# 04-MCU.net
KiCad netlist of a schematic drawn in Altium Designer
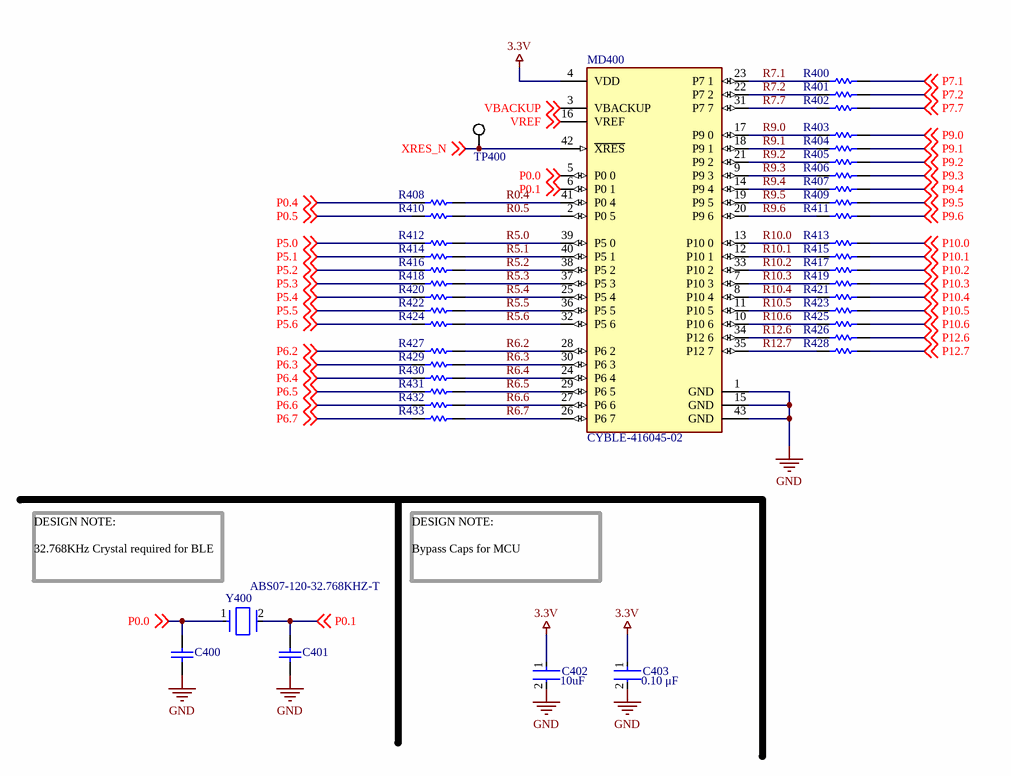
[diagram p0: 04-MCU.SchDoc]

(export (version "E")
  (design (tool "Eeschema 10.0.6"))
  (components
    (comp (ref "C400")
      (value "08055A6R0CAT2A")
      (footprint "CAPC2013X94X50LL20T25")
      (fields (field (name "MANUFACTURER") "AVX Interconnect / Elco"))
      (libsource (lib "Altium Content Vault") (part "CAP"))
    )
    (comp (ref "C401")
      (value "08055A6R0CAT2A")
      (footprint "CAPC2013X94X50LL20T25")
      (fields (field (name "MANUFACTURER") "AVX Interconnect / Elco"))
      (libsource (lib "Altium Content Vault") (part "CAP"))
    )
    (comp (ref "C402")
      (value "10uF")
      (footprint "FP-C0805C-DG-MFG")
      (description "CAP CER 10UF 10V X5R 0805")
      (fields
        (field (name "MANUFACTURER") "Kemet")
        (field (name "MANUFACTURER PART NUMBER") "C0805C106K8PACTU")
      )
      (libsource (lib "Altium Content Vault") (part "11868f565c42a9108669ba33697ecf6"))
    )
    (comp (ref "C403")
      (value "0.10 μF")
      (footprint "FP-C0805C-DN-MFG")
      (description "CAP CER 0.1UF 50V X7R 0805")
      (fields
        (field (name "MANUFACTURER") "KEMET")
        (field (name "MANUFACTURER PART NUMBER") "C0805C104K5RACTU")
      )
      (libsource (lib "Altium Content Vault") (part "b4654b650e69147ec39a6b967a45e02"))
    )
    (comp (ref "MD400")
      (value "CYBLE-416045-02")
      (footprint "FP-CYBLE-416045-02-MFG")
      (description "RF TXRX MOD BLUETOOTH TRACE ANT")
      (fields
        (field (name "OCTOPART") "https://octopart.com/cyble-416045-02-cypress+semiconductor-96386825")
        (field (name "MANUFACTURER") "Cypress Semiconductor")
      )
      (libsource (lib "Altium Content Vault") (part "10a29a4e77099fbb6f911efb04878b1"))
    )
    (comp (ref "R400")
      (value "ERA6AEB101V")
      (footprint "RESC2013X60X40ML20T25")
      (fields (field (name "MANUFACTURER") "Panasonic"))
      (libsource (lib "Altium Content Vault") (part "RES"))
    )
    (comp (ref "R401")
      (value "ERA6AEB101V")
      (footprint "RESC2013X60X40ML20T25")
      (fields (field (name "MANUFACTURER") "Panasonic"))
      (libsource (lib "Altium Content Vault") (part "RES"))
    )
    (comp (ref "R402")
      (value "ERA6AEB101V")
      (footprint "RESC2013X60X40ML20T25")
      (fields (field (name "MANUFACTURER") "Panasonic"))
      (libsource (lib "Altium Content Vault") (part "RES"))
    )
    (comp (ref "R403")
      (value "ERA6AEB101V")
      (footprint "RESC2013X60X40ML20T25")
      (fields (field (name "MANUFACTURER") "Panasonic"))
      (libsource (lib "Altium Content Vault") (part "RES"))
    )
    (comp (ref "R404")
      (value "ERA6AEB101V")
      (footprint "RESC2013X60X40ML20T25")
      (fields (field (name "MANUFACTURER") "Panasonic"))
      (libsource (lib "Altium Content Vault") (part "RES"))
    )
    (comp (ref "R405")
      (value "ERA6AEB101V")
      (footprint "RESC2013X60X40ML20T25")
      (fields (field (name "MANUFACTURER") "Panasonic"))
      (libsource (lib "Altium Content Vault") (part "RES"))
    )
    (comp (ref "R406")
      (value "ERA6AEB101V")
      (footprint "RESC2013X60X40ML20T25")
      (fields (field (name "MANUFACTURER") "Panasonic"))
      (libsource (lib "Altium Content Vault") (part "RES"))
    )
    (comp (ref "R407")
      (value "ERA6AEB101V")
      (footprint "RESC2013X60X40ML20T25")
      (fields (field (name "MANUFACTURER") "Panasonic"))
      (libsource (lib "Altium Content Vault") (part "RES"))
    )
    (comp (ref "R408")
      (value "ERA6AEB101V")
      (footprint "RESC2013X60X40ML20T25")
      (fields (field (name "MANUFACTURER") "Panasonic"))
      (libsource (lib "Altium Content Vault") (part "RES"))
    )
    (comp (ref "R409")
      (value "ERA6AEB101V")
      (footprint "RESC2013X60X40ML20T25")
      (fields (field (name "MANUFACTURER") "Panasonic"))
      (libsource (lib "Altium Content Vault") (part "RES"))
    )
    (comp (ref "R410")
      (value "ERA6AEB101V")
      (footprint "RESC2013X60X40ML20T25")
      (fields (field (name "MANUFACTURER") "Panasonic"))
      (libsource (lib "Altium Content Vault") (part "RES"))
    )
    (comp (ref "R411")
      (value "ERA6AEB101V")
      (footprint "RESC2013X60X40ML20T25")
      (fields (field (name "MANUFACTURER") "Panasonic"))
      (libsource (lib "Altium Content Vault") (part "RES"))
    )
    (comp (ref "R412")
      (value "ERA6AEB101V")
      (footprint "RESC2013X60X40ML20T25")
      (fields (field (name "MANUFACTURER") "Panasonic"))
      (libsource (lib "Altium Content Vault") (part "RES"))
    )
    (comp (ref "R413")
      (value "ERA6AEB101V")
      (footprint "RESC2013X60X40ML20T25")
      (fields (field (name "MANUFACTURER") "Panasonic"))
      (libsource (lib "Altium Content Vault") (part "RES"))
    )
    (comp (ref "R414")
      (value "ERA6AEB101V")
      (footprint "RESC2013X60X40ML20T25")
      (fields (field (name "MANUFACTURER") "Panasonic"))
      (libsource (lib "Altium Content Vault") (part "RES"))
    )
    (comp (ref "R415")
      (value "ERA6AEB101V")
      (footprint "RESC2013X60X40ML20T25")
      (fields (field (name "MANUFACTURER") "Panasonic"))
      (libsource (lib "Altium Content Vault") (part "RES"))
    )
    (comp (ref "R416")
      (value "ERA6AEB101V")
      (footprint "RESC2013X60X40ML20T25")
      (fields (field (name "MANUFACTURER") "Panasonic"))
      (libsource (lib "Altium Content Vault") (part "RES"))
    )
    (comp (ref "R417")
      (value "ERA6AEB101V")
      (footprint "RESC2013X60X40ML20T25")
      (fields (field (name "MANUFACTURER") "Panasonic"))
      (libsource (lib "Altium Content Vault") (part "RES"))
    )
    (comp (ref "R418")
      (value "ERA6AEB101V")
      (footprint "RESC2013X60X40ML20T25")
      (fields (field (name "MANUFACTURER") "Panasonic"))
      (libsource (lib "Altium Content Vault") (part "RES"))
    )
    (comp (ref "R419")
      (value "ERA6AEB101V")
      (footprint "RESC2013X60X40ML20T25")
      (fields (field (name "MANUFACTURER") "Panasonic"))
      (libsource (lib "Altium Content Vault") (part "RES"))
    )
    (comp (ref "R420")
      (value "ERA6AEB101V")
      (footprint "RESC2013X60X40ML20T25")
      (fields (field (name "MANUFACTURER") "Panasonic"))
      (libsource (lib "Altium Content Vault") (part "RES"))
    )
    (comp (ref "R421")
      (value "ERA6AEB101V")
      (footprint "RESC2013X60X40ML20T25")
      (fields (field (name "MANUFACTURER") "Panasonic"))
      (libsource (lib "Altium Content Vault") (part "RES"))
    )
    (comp (ref "R422")
      (value "ERA6AEB101V")
      (footprint "RESC2013X60X40ML20T25")
      (fields (field (name "MANUFACTURER") "Panasonic"))
      (libsource (lib "Altium Content Vault") (part "RES"))
    )
    (comp (ref "R423")
      (value "ERA6AEB101V")
      (footprint "RESC2013X60X40ML20T25")
      (fields (field (name "MANUFACTURER") "Panasonic"))
      (libsource (lib "Altium Content Vault") (part "RES"))
    )
    (comp (ref "R424")
      (value "ERA6AEB101V")
      (footprint "RESC2013X60X40ML20T25")
      (fields (field (name "MANUFACTURER") "Panasonic"))
      (libsource (lib "Altium Content Vault") (part "RES"))
    )
    (comp (ref "R425")
      (value "ERA6AEB101V")
      (footprint "RESC2013X60X40ML20T25")
      (fields (field (name "MANUFACTURER") "Panasonic"))
      (libsource (lib "Altium Content Vault") (part "RES"))
    )
    (comp (ref "R426")
      (value "ERA6AEB101V")
      (footprint "RESC2013X60X40ML20T25")
      (fields (field (name "MANUFACTURER") "Panasonic"))
      (libsource (lib "Altium Content Vault") (part "RES"))
    )
    (comp (ref "R427")
      (value "ERA6AEB101V")
      (footprint "RESC2013X60X40ML20T25")
      (fields (field (name "MANUFACTURER") "Panasonic"))
      (libsource (lib "Altium Content Vault") (part "RES"))
    )
    (comp (ref "R428")
      (value "ERA6AEB101V")
      (footprint "RESC2013X60X40ML20T25")
      (fields (field (name "MANUFACTURER") "Panasonic"))
      (libsource (lib "Altium Content Vault") (part "RES"))
    )
    (comp (ref "R429")
      (value "ERA6AEB101V")
      (footprint "RESC2013X60X40ML20T25")
      (fields (field (name "MANUFACTURER") "Panasonic"))
      (libsource (lib "Altium Content Vault") (part "RES"))
    )
    (comp (ref "R430")
      (value "ERA6AEB101V")
      (footprint "RESC2013X60X40ML20T25")
      (fields (field (name "MANUFACTURER") "Panasonic"))
      (libsource (lib "Altium Content Vault") (part "RES"))
    )
    (comp (ref "R431")
      (value "ERA6AEB101V")
      (footprint "RESC2013X60X40ML20T25")
      (fields (field (name "MANUFACTURER") "Panasonic"))
      (libsource (lib "Altium Content Vault") (part "RES"))
    )
    (comp (ref "R432")
      (value "ERA6AEB101V")
      (footprint "RESC2013X60X40ML20T25")
      (fields (field (name "MANUFACTURER") "Panasonic"))
      (libsource (lib "Altium Content Vault") (part "RES"))
    )
    (comp (ref "R433")
      (value "ERA6AEB101V")
      (footprint "RESC2013X60X40ML20T25")
      (fields (field (name "MANUFACTURER") "Panasonic"))
      (libsource (lib "Altium Content Vault") (part "RES"))
    )
    (comp (ref "TP400")
      (value "5019")
      (footprint "KSTN-5019_V")
      (description "Test Point, 1 Position SMD, RoHS, Tape and Reel")
      (libsource (lib "Altium Content Vault") (part "TESTPOINT_WHITE"))
    )
    (comp (ref "Y400")
      (value "ABS07-120-32.768KHZ-T")
      (footprint "FP-ABS07-120-MFG")
      (description "CRYSTAL 32.7680KHZ 6PF SMD")
      (fields (field (name "TOLERANCE") "20ppm"))
      (libsource (lib "Altium Content Vault") (part "c23a69dc6c9e2f18f2079038eb95dd1"))
    )
  )
  (nets
    (net (code "1") (name "/R0.4") (class "Default")
      (node (ref "MD400") (pin "41") (pinfunction "P0_4_41") (pintype "bidirectional"))
      (node (ref "R408") (pin "2") (pinfunction "2_2") (pintype "passive"))
    )
    (net (code "2") (name "/R0.5") (class "Default")
      (node (ref "MD400") (pin "2") (pinfunction "P0_5_2") (pintype "bidirectional"))
      (node (ref "R410") (pin "2") (pinfunction "2_2") (pintype "passive"))
    )
    (net (code "3") (name "/R5.0") (class "Default")
      (node (ref "MD400") (pin "39") (pinfunction "P5_0_39") (pintype "bidirectional"))
      (node (ref "R412") (pin "2") (pinfunction "2_2") (pintype "passive"))
    )
    (net (code "4") (name "/R5.1") (class "Default")
      (node (ref "MD400") (pin "40") (pinfunction "P5_1_40") (pintype "bidirectional"))
      (node (ref "R414") (pin "2") (pinfunction "2_2") (pintype "passive"))
    )
    (net (code "5") (name "/R5.2") (class "Default")
      (node (ref "MD400") (pin "38") (pinfunction "P5_2_38") (pintype "bidirectional"))
      (node (ref "R416") (pin "2") (pinfunction "2_2") (pintype "passive"))
    )
    (net (code "6") (name "/R5.3") (class "Default")
      (node (ref "MD400") (pin "37") (pinfunction "P5_3_37") (pintype "bidirectional"))
      (node (ref "R418") (pin "2") (pinfunction "2_2") (pintype "passive"))
    )
    (net (code "7") (name "/R5.4") (class "Default")
      (node (ref "MD400") (pin "25") (pinfunction "P5_4_25") (pintype "bidirectional"))
      (node (ref "R420") (pin "2") (pinfunction "2_2") (pintype "passive"))
    )
    (net (code "8") (name "/R5.5") (class "Default")
      (node (ref "MD400") (pin "36") (pinfunction "P5_5_36") (pintype "bidirectional"))
      (node (ref "R422") (pin "2") (pinfunction "2_2") (pintype "passive"))
    )
    (net (code "9") (name "/R5.6") (class "Default")
      (node (ref "MD400") (pin "32") (pinfunction "P5_6_32") (pintype "bidirectional"))
      (node (ref "R424") (pin "2") (pinfunction "2_2") (pintype "passive"))
    )
    (net (code "10") (name "/R6.2") (class "Default")
      (node (ref "MD400") (pin "28") (pinfunction "P6_2_28") (pintype "bidirectional"))
      (node (ref "R427") (pin "2") (pinfunction "2_2") (pintype "passive"))
    )
    (net (code "11") (name "/R6.3") (class "Default")
      (node (ref "MD400") (pin "30") (pinfunction "P6_3_30") (pintype "bidirectional"))
      (node (ref "R429") (pin "2") (pinfunction "2_2") (pintype "passive"))
    )
    (net (code "12") (name "/R6.4") (class "Default")
      (node (ref "MD400") (pin "24") (pinfunction "P6_4_24") (pintype "bidirectional"))
      (node (ref "R430") (pin "2") (pinfunction "2_2") (pintype "passive"))
    )
    (net (code "13") (name "/R6.5") (class "Default")
      (node (ref "MD400") (pin "29") (pinfunction "P6_5_29") (pintype "bidirectional"))
      (node (ref "R431") (pin "2") (pinfunction "2_2") (pintype "passive"))
    )
    (net (code "14") (name "/R6.6") (class "Default")
      (node (ref "MD400") (pin "27") (pinfunction "P6_6_27") (pintype "bidirectional"))
      (node (ref "R432") (pin "2") (pinfunction "2_2") (pintype "passive"))
    )
    (net (code "15") (name "/R6.7") (class "Default")
      (node (ref "MD400") (pin "26") (pinfunction "P6_7_26") (pintype "bidirectional"))
      (node (ref "R433") (pin "2") (pinfunction "2_2") (pintype "passive"))
    )
    (net (code "16") (name "/R7.1") (class "Default")
      (node (ref "MD400") (pin "23") (pinfunction "P7_1_23") (pintype "bidirectional"))
      (node (ref "R400") (pin "1") (pinfunction "1_1") (pintype "passive"))
    )
    (net (code "17") (name "/R7.2") (class "Default")
      (node (ref "MD400") (pin "22") (pinfunction "P7_2_22") (pintype "bidirectional"))
      (node (ref "R401") (pin "1") (pinfunction "1_1") (pintype "passive"))
    )
    (net (code "18") (name "/R7.7") (class "Default")
      (node (ref "MD400") (pin "31") (pinfunction "P7_7_31") (pintype "bidirectional"))
      (node (ref "R402") (pin "1") (pinfunction "1_1") (pintype "passive"))
    )
    (net (code "19") (name "/R9.0") (class "Default")
      (node (ref "MD400") (pin "17") (pinfunction "P9_0_17") (pintype "bidirectional"))
      (node (ref "R403") (pin "1") (pinfunction "1_1") (pintype "passive"))
    )
    (net (code "20") (name "/R9.1") (class "Default")
      (node (ref "MD400") (pin "18") (pinfunction "P9_1_18") (pintype "bidirectional"))
      (node (ref "R404") (pin "1") (pinfunction "1_1") (pintype "passive"))
    )
    (net (code "21") (name "/R9.2") (class "Default")
      (node (ref "MD400") (pin "21") (pinfunction "P9_2_21") (pintype "bidirectional"))
      (node (ref "R405") (pin "1") (pinfunction "1_1") (pintype "passive"))
    )
    (net (code "22") (name "/R9.3") (class "Default")
      (node (ref "MD400") (pin "9") (pinfunction "P9_3_9") (pintype "bidirectional"))
      (node (ref "R406") (pin "1") (pinfunction "1_1") (pintype "passive"))
    )
    (net (code "23") (name "/R9.4") (class "Default")
      (node (ref "MD400") (pin "14") (pinfunction "P9_4_14") (pintype "bidirectional"))
      (node (ref "R407") (pin "1") (pinfunction "1_1") (pintype "passive"))
    )
    (net (code "24") (name "/R9.5") (class "Default")
      (node (ref "MD400") (pin "19") (pinfunction "P9_5_19") (pintype "bidirectional"))
      (node (ref "R409") (pin "1") (pinfunction "1_1") (pintype "passive"))
    )
    (net (code "25") (name "/R9.6") (class "Default")
      (node (ref "MD400") (pin "20") (pinfunction "P9_6_20") (pintype "bidirectional"))
      (node (ref "R411") (pin "1") (pinfunction "1_1") (pintype "passive"))
    )
    (net (code "26") (name "/R10.0") (class "Default")
      (node (ref "MD400") (pin "13") (pinfunction "P10_0_13") (pintype "bidirectional"))
      (node (ref "R413") (pin "1") (pinfunction "1_1") (pintype "passive"))
    )
    (net (code "27") (name "/R10.1") (class "Default")
      (node (ref "MD400") (pin "12") (pinfunction "P10_1_12") (pintype "bidirectional"))
      (node (ref "R415") (pin "1") (pinfunction "1_1") (pintype "passive"))
    )
    (net (code "28") (name "/R10.2") (class "Default")
      (node (ref "MD400") (pin "33") (pinfunction "P10_2_33") (pintype "bidirectional"))
      (node (ref "R417") (pin "1") (pinfunction "1_1") (pintype "passive"))
    )
    (net (code "29") (name "/R10.3") (class "Default")
      (node (ref "MD400") (pin "7") (pinfunction "P10_3_7") (pintype "bidirectional"))
      (node (ref "R419") (pin "1") (pinfunction "1_1") (pintype "passive"))
    )
    (net (code "30") (name "/R10.4") (class "Default")
      (node (ref "MD400") (pin "8") (pinfunction "P10_4_8") (pintype "bidirectional"))
      (node (ref "R421") (pin "1") (pinfunction "1_1") (pintype "passive"))
    )
    (net (code "31") (name "/R10.5") (class "Default")
      (node (ref "MD400") (pin "11") (pinfunction "P10_5_11") (pintype "bidirectional"))
      (node (ref "R423") (pin "1") (pinfunction "1_1") (pintype "passive"))
    )
    (net (code "32") (name "/R10.6") (class "Default")
      (node (ref "MD400") (pin "10") (pinfunction "P10_6_10") (pintype "bidirectional"))
      (node (ref "R425") (pin "1") (pinfunction "1_1") (pintype "passive"))
    )
    (net (code "33") (name "/R12.6") (class "Default")
      (node (ref "MD400") (pin "34") (pinfunction "P12_6_34") (pintype "bidirectional"))
      (node (ref "R426") (pin "1") (pinfunction "1_1") (pintype "passive"))
    )
    (net (code "34") (name "/R12.7") (class "Default")
      (node (ref "MD400") (pin "35") (pinfunction "P12_7_35") (pintype "bidirectional"))
      (node (ref "R428") (pin "1") (pinfunction "1_1") (pintype "passive"))
    )
    (net (code "35") (name "3.3V") (class "Default")
      (node (ref "C402") (pin "1") (pinfunction "1_1") (pintype "passive"))
      (node (ref "C403") (pin "1") (pinfunction "1_1") (pintype "passive"))
      (node (ref "MD400") (pin "4") (pinfunction "VDD_4") (pintype "power_in"))
    )
    (net (code "36") (name "GND") (class "Default")
      (node (ref "C400") (pin "1") (pinfunction "1_1") (pintype "passive"))
      (node (ref "C401") (pin "1") (pinfunction "1_1") (pintype "passive"))
      (node (ref "C402") (pin "2") (pinfunction "2_2") (pintype "passive"))
      (node (ref "C403") (pin "2") (pinfunction "2_2") (pintype "passive"))
      (node (ref "MD400") (pin "1") (pinfunction "GND_1") (pintype "power_in"))
      (node (ref "MD400") (pin "15") (pinfunction "GND_15") (pintype "power_in"))
      (node (ref "MD400") (pin "43") (pinfunction "GND_43") (pintype "power_in"))
    )
    (net (code "37") (name "P0.0") (class "Default")
      (node (ref "C400") (pin "2") (pinfunction "2_2") (pintype "passive"))
      (node (ref "MD400") (pin "5") (pinfunction "P0_0_5") (pintype "bidirectional"))
      (node (ref "Y400") (pin "1") (pinfunction "1_1") (pintype "passive"))
    )
    (net (code "38") (name "P0.1") (class "Default")
      (node (ref "C401") (pin "2") (pinfunction "2_2") (pintype "passive"))
      (node (ref "MD400") (pin "6") (pinfunction "P0_1_6") (pintype "bidirectional"))
      (node (ref "Y400") (pin "2") (pinfunction "2_2") (pintype "passive"))
    )
    (net (code "39") (name "P0.4") (class "Default")
      (node (ref "R408") (pin "1") (pinfunction "1_1") (pintype "passive"))
    )
    (net (code "40") (name "P0.5") (class "Default")
      (node (ref "R410") (pin "1") (pinfunction "1_1") (pintype "passive"))
    )
    (net (code "41") (name "P5.0") (class "Default")
      (node (ref "R412") (pin "1") (pinfunction "1_1") (pintype "passive"))
    )
    (net (code "42") (name "P5.1") (class "Default")
      (node (ref "R414") (pin "1") (pinfunction "1_1") (pintype "passive"))
    )
    (net (code "43") (name "P5.2") (class "Default")
      (node (ref "R416") (pin "1") (pinfunction "1_1") (pintype "passive"))
    )
    (net (code "44") (name "P5.3") (class "Default")
      (node (ref "R418") (pin "1") (pinfunction "1_1") (pintype "passive"))
    )
    (net (code "45") (name "P5.4") (class "Default")
      (node (ref "R420") (pin "1") (pinfunction "1_1") (pintype "passive"))
    )
    (net (code "46") (name "P5.5") (class "Default")
      (node (ref "R422") (pin "1") (pinfunction "1_1") (pintype "passive"))
    )
    (net (code "47") (name "P5.6") (class "Default")
      (node (ref "R424") (pin "1") (pinfunction "1_1") (pintype "passive"))
    )
    (net (code "48") (name "P6.2") (class "Default")
      (node (ref "R427") (pin "1") (pinfunction "1_1") (pintype "passive"))
    )
    (net (code "49") (name "P6.3") (class "Default")
      (node (ref "R429") (pin "1") (pinfunction "1_1") (pintype "passive"))
    )
    (net (code "50") (name "P6.4") (class "Default")
      (node (ref "R430") (pin "1") (pinfunction "1_1") (pintype "passive"))
    )
    (net (code "51") (name "P6.5") (class "Default")
      (node (ref "R431") (pin "1") (pinfunction "1_1") (pintype "passive"))
    )
    (net (code "52") (name "P6.6") (class "Default")
      (node (ref "R432") (pin "1") (pinfunction "1_1") (pintype "passive"))
    )
    (net (code "53") (name "P6.7") (class "Default")
      (node (ref "R433") (pin "1") (pinfunction "1_1") (pintype "passive"))
    )
    (net (code "54") (name "P7.1") (class "Default")
      (node (ref "R400") (pin "2") (pinfunction "2_2") (pintype "passive"))
    )
    (net (code "55") (name "P7.2") (class "Default")
      (node (ref "R401") (pin "2") (pinfunction "2_2") (pintype "passive"))
    )
    (net (code "56") (name "P7.7") (class "Default")
      (node (ref "R402") (pin "2") (pinfunction "2_2") (pintype "passive"))
    )
    (net (code "57") (name "P9.0") (class "Default")
      (node (ref "R403") (pin "2") (pinfunction "2_2") (pintype "passive"))
    )
    (net (code "58") (name "P9.1") (class "Default")
      (node (ref "R404") (pin "2") (pinfunction "2_2") (pintype "passive"))
    )
    (net (code "59") (name "P9.2") (class "Default")
      (node (ref "R405") (pin "2") (pinfunction "2_2") (pintype "passive"))
    )
    (net (code "60") (name "P9.3") (class "Default")
      (node (ref "R406") (pin "2") (pinfunction "2_2") (pintype "passive"))
    )
    (net (code "61") (name "P9.4") (class "Default")
      (node (ref "R407") (pin "2") (pinfunction "2_2") (pintype "passive"))
    )
    (net (code "62") (name "P9.5") (class "Default")
      (node (ref "R409") (pin "2") (pinfunction "2_2") (pintype "passive"))
    )
    (net (code "63") (name "P9.6") (class "Default")
      (node (ref "R411") (pin "2") (pinfunction "2_2") (pintype "passive"))
    )
    (net (code "64") (name "P10.0") (class "Default")
      (node (ref "R413") (pin "2") (pinfunction "2_2") (pintype "passive"))
    )
    (net (code "65") (name "P10.1") (class "Default")
      (node (ref "R415") (pin "2") (pinfunction "2_2") (pintype "passive"))
    )
    (net (code "66") (name "P10.2") (class "Default")
      (node (ref "R417") (pin "2") (pinfunction "2_2") (pintype "passive"))
    )
    (net (code "67") (name "P10.3") (class "Default")
      (node (ref "R419") (pin "2") (pinfunction "2_2") (pintype "passive"))
    )
    (net (code "68") (name "P10.4") (class "Default")
      (node (ref "R421") (pin "2") (pinfunction "2_2") (pintype "passive"))
    )
    (net (code "69") (name "P10.5") (class "Default")
      (node (ref "R423") (pin "2") (pinfunction "2_2") (pintype "passive"))
    )
    (net (code "70") (name "P10.6") (class "Default")
      (node (ref "R425") (pin "2") (pinfunction "2_2") (pintype "passive"))
    )
    (net (code "71") (name "P12.6") (class "Default")
      (node (ref "R426") (pin "2") (pinfunction "2_2") (pintype "passive"))
    )
    (net (code "72") (name "P12.7") (class "Default")
      (node (ref "R428") (pin "2") (pinfunction "2_2") (pintype "passive"))
    )
    (net (code "73") (name "VBACKUP") (class "Default")
      (node (ref "MD400") (pin "3") (pinfunction "VBACKUP_3") (pintype "power_in"))
    )
    (net (code "74") (name "VREF") (class "Default")
      (node (ref "MD400") (pin "16") (pinfunction "VREF_16") (pintype "power_in"))
    )
    (net (code "75") (name "XRES_N") (class "Default")
      (node (ref "MD400") (pin "42") (pinfunction "~{XRES}_42") (pintype "input"))
      (node (ref "TP400") (pin "1") (pinfunction "1_1") (pintype "passive"))
    )
  )
)
